# DCDC-LMR16030.net
KiCad netlist of a schematic drawn in Altium Designer
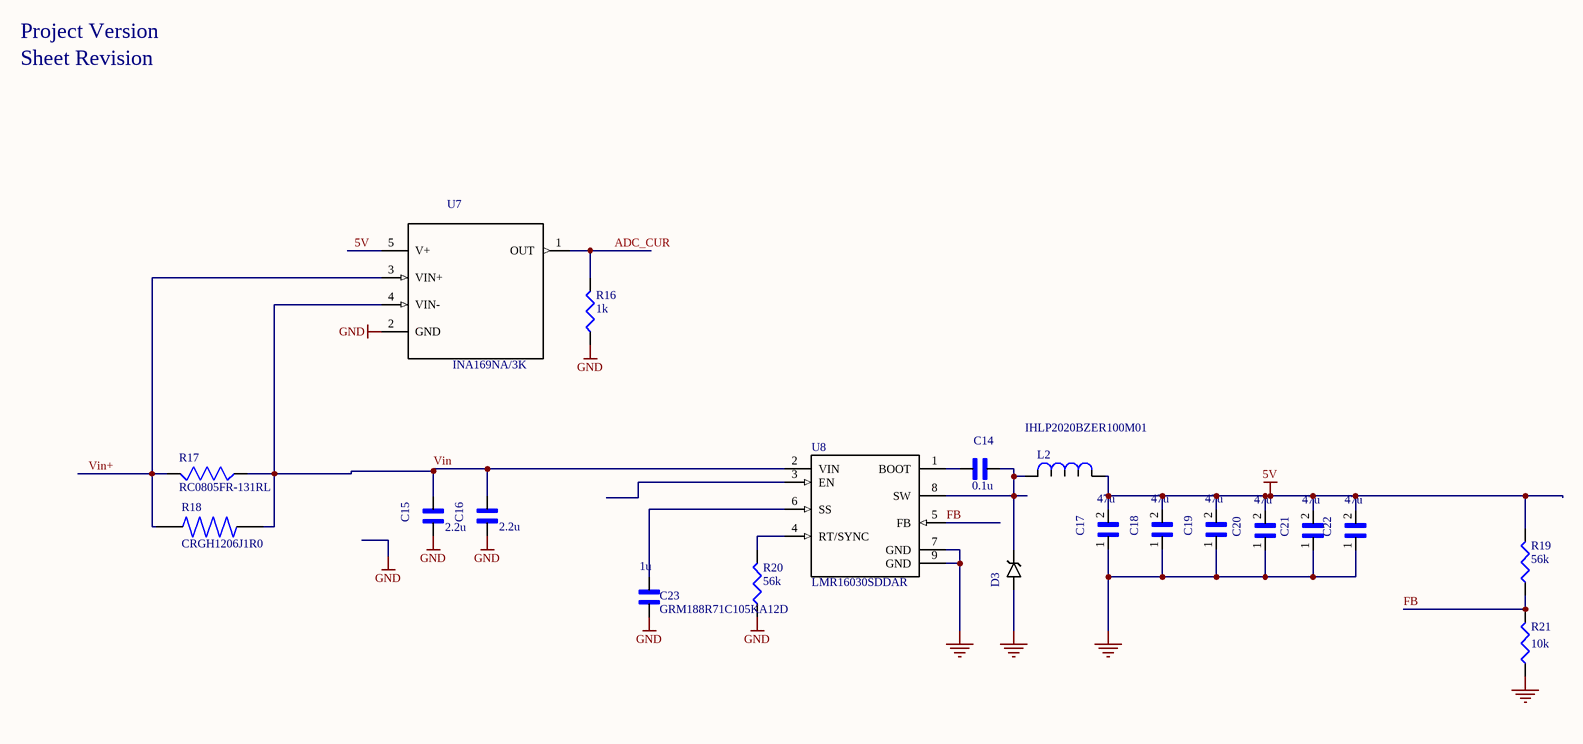
[diagram p0: DCDC-LMR16030.SchDoc]

(export (version "E")
  (design (tool "Eeschema 10.0.6"))
  (components
    (comp (ref "C14")
      (value "0.1u")
      (footprint "*CAPC1608X90")
      (description "Cap Thin Film 0.1uf 50v 0603")
      (fields (field (name "MF") "AVX") (field (name "MP") "GX035C104MAT2-500 or CL10B104JB8NNNC"))
      (libsource (lib "lib") (part "GX035C104MAT2-500"))
    )
    (comp (ref "C15")
      (value "2.2u")
      (footprint "*CAP3216X125N")
      (description "1206 2.2 uF 50 V В±10% Tolerance X7R SMT Multilayer Ceramic Capacitor")
      (fields (field (name "MF") "Murata Electronics") (field (name "MP") "GRM31CR71H225KA88L"))
      (libsource (lib "lib") (part "GRM31CR71H225KA88L"))
    )
    (comp (ref "C16")
      (value "2.2u")
      (footprint "*CAP3216X125N")
      (description "1206 2.2 uF 50 V В±10% Tolerance X7R SMT Multilayer Ceramic Capacitor")
      (fields (field (name "MF") "Murata Electronics") (field (name "MP") "GRM31CR71H225KA88L"))
      (libsource (lib "lib") (part "GRM31CR71H225KA88L"))
    )
    (comp (ref "C17")
      (value "47u")
      (footprint "*CAPC3216X125N")
      (description "Multilayer Ceramic Capacitor, GRM Series, 47 - F, - 10%, X5R, 10 V, 1206 [3216 Metric]")
      (fields (field (name "MF") "Murata Electronics") (field (name "MP") "GRM31CR61A476KE15L"))
      (libsource (lib "lib") (part "GRM31CR61A476KE15L"))
    )
    (comp (ref "C18")
      (value "47u")
      (footprint "*CAPC3216X125N")
      (description "Multilayer Ceramic Capacitor, GRM Series, 47 - F, - 10%, X5R, 10 V, 1206 [3216 Metric]")
      (fields (field (name "MF") "Murata Electronics") (field (name "MP") "GRM31CR61A476KE15L"))
      (libsource (lib "lib") (part "GRM31CR61A476KE15L"))
    )
    (comp (ref "C19")
      (value "47u")
      (footprint "*CAPC3216X125N")
      (description "Multilayer Ceramic Capacitor, GRM Series, 47 - F, - 10%, X5R, 10 V, 1206 [3216 Metric]")
      (fields (field (name "MF") "Murata Electronics") (field (name "MP") "GRM31CR61A476KE15L"))
      (libsource (lib "lib") (part "GRM31CR61A476KE15L"))
    )
    (comp (ref "C20")
      (value "47u")
      (footprint "*CAPC3216X125N")
      (description "Multilayer Ceramic Capacitor, GRM Series, 47 - F, - 10%, X5R, 10 V, 1206 [3216 Metric]")
      (fields (field (name "MF") "Murata Electronics") (field (name "MP") "GRM31CR61A476KE15L"))
      (libsource (lib "lib") (part "GRM31CR61A476KE15L"))
    )
    (comp (ref "C21")
      (value "47u")
      (footprint "*CAPC3216X125N")
      (description "Multilayer Ceramic Capacitor, GRM Series, 47 - F, - 10%, X5R, 10 V, 1206 [3216 Metric]")
      (fields (field (name "MF") "Murata Electronics") (field (name "MP") "GRM31CR61A476KE15L"))
      (libsource (lib "lib") (part "GRM31CR61A476KE15L"))
    )
    (comp (ref "C22")
      (value "47u")
      (footprint "*CAPC3216X125N")
      (description "Multilayer Ceramic Capacitor, GRM Series, 47 - F, - 10%, X5R, 10 V, 1206 [3216 Metric]")
      (fields (field (name "MF") "Murata Electronics") (field (name "MP") "GRM31CR61A476KE15L"))
      (libsource (lib "lib") (part "GRM31CR61A476KE15L"))
    )
    (comp (ref "C23")
      (value "GRM188R71C105KA12D")
      (footprint "CAPC1608X90N")
      (description "SMD Capacitor X7R(EIA) with Capacitance: 1.0uF Tol. 10%. Rated Voltage: 16Vdc")
      (fields (field (name "MF") "Murata Electronics") (field (name "ALTIUM_VALUE") "1u"))
      (libsource (lib "lib") (part "GRM188R71C105KA12D"))
    )
    (comp (ref "D3")
      (value "SK56")
      (footprint "*SMB_P6SMB62AT3G(Primary)")
      (description "Диод Шоттки 5А 60В [SMB / DO-214AA]")
      (fields (field (name "MF") "Littelfuse Inc."))
      (libsource (lib "lib") (part "SK56"))
    )
    (comp (ref "L2")
      (value "IHLP2020BZER100M01")
      (footprint "IHLP")
      (description "10ÂµH Shielded Molded Inductor 2.3A 199mOhm Max Nonstandard")
      (fields (field (name "MF") "Vishay Dale"))
      (libsource (lib "lib") (part "IHLP2020BZER100M01"))
    )
    (comp (ref "R16")
      (value "1k")
      (footprint "J1-0603")
      (description "Resistor")
      (fields (field (name "Comment") "Res3") (field (name "PUBLISHER") "Altium Limited"))
      (libsource (lib "Miscellaneous Devices") (part "Res3"))
    )
    (comp (ref "R17")
      (value "RC0805FR-131RL")
      (footprint "RESC2012X60")
      (description "RC Series 0805 0.125 W 2 kOhms 5% В±100 ppm/В°C SMT Thick Film Chip Resistor")
      (fields (field (name "MF") "{'manufacturer': u'Yageo'}"))
      (libsource (lib "SnapEDA_Library") (part "RC0805FR-131RL"))
    )
    (comp (ref "R18")
      (value "CRGH1206J1R0")
      (footprint "RESC3115X65N")
      (description "Res Thick Film 1206 1 Ohm 5% 1/2W В±200ppm/В°C Molded SMD SMD T/R")
      (fields (field (name "MF") "{'manufacturer': u'TE Connectivity'}"))
      (libsource (lib "SnapEDA_Library") (part "CRGH1206J1R0"))
    )
    (comp (ref "R19")
      (value "56k")
      (footprint "J1-0603")
      (description "Resistor")
      (fields (field (name "MP") "RC0603FR-0756KL") (field (name "Comment") "Res3"))
      (libsource (lib "Miscellaneous Devices") (part "Res3"))
    )
    (comp (ref "R20")
      (value "56k")
      (footprint "J1-0603")
      (description "Resistor")
      (fields (field (name "MP") "RC0603FR-0756KL") (field (name "Comment") "Res3"))
      (libsource (lib "Miscellaneous Devices") (part "Res3"))
    )
    (comp (ref "R21")
      (value "10k")
      (footprint "J1-0603")
      (description "10 kOhms 1 0.1 W 1 10 W Chip Resistor 0603 1608 Metric Thick Film")
      (fields (field (name "MF") "Yageo or NXP") (field (name "MP") "10K 1% 0603"))
      (libsource (lib "CAN_NODE_MINI") (part "RC0603FR-0710KL"))
    )
    (comp (ref "U7")
      (value "INA169NA/3K")
      (footprint "*SOT95P280X145-5N")
      (description "Current Monitor Regulator High-Side SOT-23-5")
      (fields (field (name "MF") "Texas Instruments"))
      (libsource (lib "lib") (part "INA169NA/3K"))
    )
    (comp (ref "U8")
      (value "LMR16030SDDAR")
      (footprint "*SOIC127P600X170-9N - duplicate")
      (fields (field (name "MF") "Texas Instruments"))
      (libsource (lib "lib") (part "LMR16030SDDAR"))
    )
  )
  (nets
    (net (code "1") (name "/ADC_CUR") (class "Default")
      (node (ref "R16") (pin "2") (pinfunction "2_2") (pintype "passive"))
      (node (ref "U7") (pin "1") (pinfunction "OUT_1") (pintype "output"))
    )
    (net (code "2") (name "/FB") (class "Default")
      (node (ref "R19") (pin "1") (pinfunction "1_1") (pintype "passive"))
      (node (ref "R21") (pin "2") (pinfunction "2_2") (pintype "passive"))
      (node (ref "U8") (pin "5") (pinfunction "FB_5") (pintype "input"))
    )
    (net (code "3") (name "/Vin") (class "Default")
      (node (ref "C15") (pin "1") (pinfunction "1_1") (pintype "passive"))
      (node (ref "C16") (pin "1") (pinfunction "1_1") (pintype "passive"))
      (node (ref "R17") (pin "2") (pinfunction "2_2") (pintype "passive"))
      (node (ref "R18") (pin "2") (pinfunction "2_2") (pintype "passive"))
      (node (ref "U7") (pin "4") (pinfunction "VIN-_4") (pintype "input"))
      (node (ref "U8") (pin "2") (pinfunction "VIN_2") (pintype "power_in"))
    )
    (net (code "4") (name "/Vin+") (class "Default")
      (node (ref "R17") (pin "1") (pinfunction "1_1") (pintype "passive"))
      (node (ref "R18") (pin "1") (pinfunction "1_1") (pintype "passive"))
      (node (ref "U7") (pin "3") (pinfunction "VIN+_3") (pintype "input"))
    )
    (net (code "5") (name "5V") (class "Default")
      (node (ref "C17") (pin "2") (pinfunction "2_2") (pintype "passive"))
      (node (ref "C18") (pin "2") (pinfunction "2_2") (pintype "passive"))
      (node (ref "C19") (pin "2") (pinfunction "2_2") (pintype "passive"))
      (node (ref "C20") (pin "2") (pinfunction "2_2") (pintype "passive"))
      (node (ref "C21") (pin "2") (pinfunction "2_2") (pintype "passive"))
      (node (ref "C22") (pin "2") (pinfunction "2_2") (pintype "passive"))
      (node (ref "L2") (pin "1") (pinfunction "1_1") (pintype "passive"))
      (node (ref "R19") (pin "2") (pinfunction "2_2") (pintype "passive"))
      (node (ref "U7") (pin "5") (pinfunction "V+_5") (pintype "power_in"))
    )
    (net (code "6") (name "GND") (class "Default")
      (node (ref "C15") (pin "2") (pinfunction "2_2") (pintype "passive"))
      (node (ref "C16") (pin "2") (pinfunction "2_2") (pintype "passive"))
      (node (ref "C17") (pin "1") (pinfunction "1_1") (pintype "passive"))
      (node (ref "C18") (pin "1") (pinfunction "1_1") (pintype "passive"))
      (node (ref "C19") (pin "1") (pinfunction "1_1") (pintype "passive"))
      (node (ref "C20") (pin "1") (pinfunction "1_1") (pintype "passive"))
      (node (ref "C21") (pin "1") (pinfunction "1_1") (pintype "passive"))
      (node (ref "C22") (pin "1") (pinfunction "1_1") (pintype "passive"))
      (node (ref "C23") (pin "1") (pinfunction "1_1") (pintype "passive"))
      (node (ref "D3") (pin "A") (pinfunction "A_A") (pintype "power_in"))
      (node (ref "R16") (pin "1") (pinfunction "1_1") (pintype "passive"))
      (node (ref "R20") (pin "1") (pinfunction "1_1") (pintype "passive"))
      (node (ref "R21") (pin "1") (pinfunction "1_1") (pintype "passive"))
      (node (ref "U7") (pin "2") (pinfunction "GND_2") (pintype "passive"))
      (node (ref "U8") (pin "7") (pinfunction "GND_7") (pintype "power_in"))
      (node (ref "U8") (pin "9") (pinfunction "GND_9") (pintype "power_in"))
    )
    (net (code "7") (name "Net-(U8-BOOT)") (class "Default")
      (node (ref "C14") (pin "2") (pinfunction "2_2") (pintype "passive"))
      (node (ref "U8") (pin "1") (pinfunction "BOOT_1") (pintype "power_in"))
    )
    (net (code "8") (name "Net-(U8-RT{slash}SYNC)") (class "Default")
      (node (ref "R20") (pin "2") (pinfunction "2_2") (pintype "passive"))
      (node (ref "U8") (pin "4") (pinfunction "RT/SYNC_4") (pintype "input"))
    )
    (net (code "9") (name "Net-(U8-SS)") (class "Default")
      (node (ref "C23") (pin "2") (pinfunction "2_2") (pintype "passive"))
      (node (ref "U8") (pin "6") (pinfunction "SS_6") (pintype "input"))
    )
    (net (code "10") (name "Net-(U8-SW)") (class "Default")
      (node (ref "C14") (pin "1") (pinfunction "1_1") (pintype "passive"))
      (node (ref "D3") (pin "C") (pinfunction "C_C") (pintype "power_in"))
      (node (ref "L2") (pin "2") (pinfunction "2_2") (pintype "passive"))
      (node (ref "U8") (pin "8") (pinfunction "SW_8") (pintype "power_in"))
    )
    (net (code "11") (name "unconnected-(U8-EN-Pad3)") (class "Default")
      (node (ref "U8") (pin "3") (pinfunction "EN_3") (pintype "input"))
    )
  )
)
